# Ventilator.net
KiCad netlist of a schematic drawn in Altium Designer
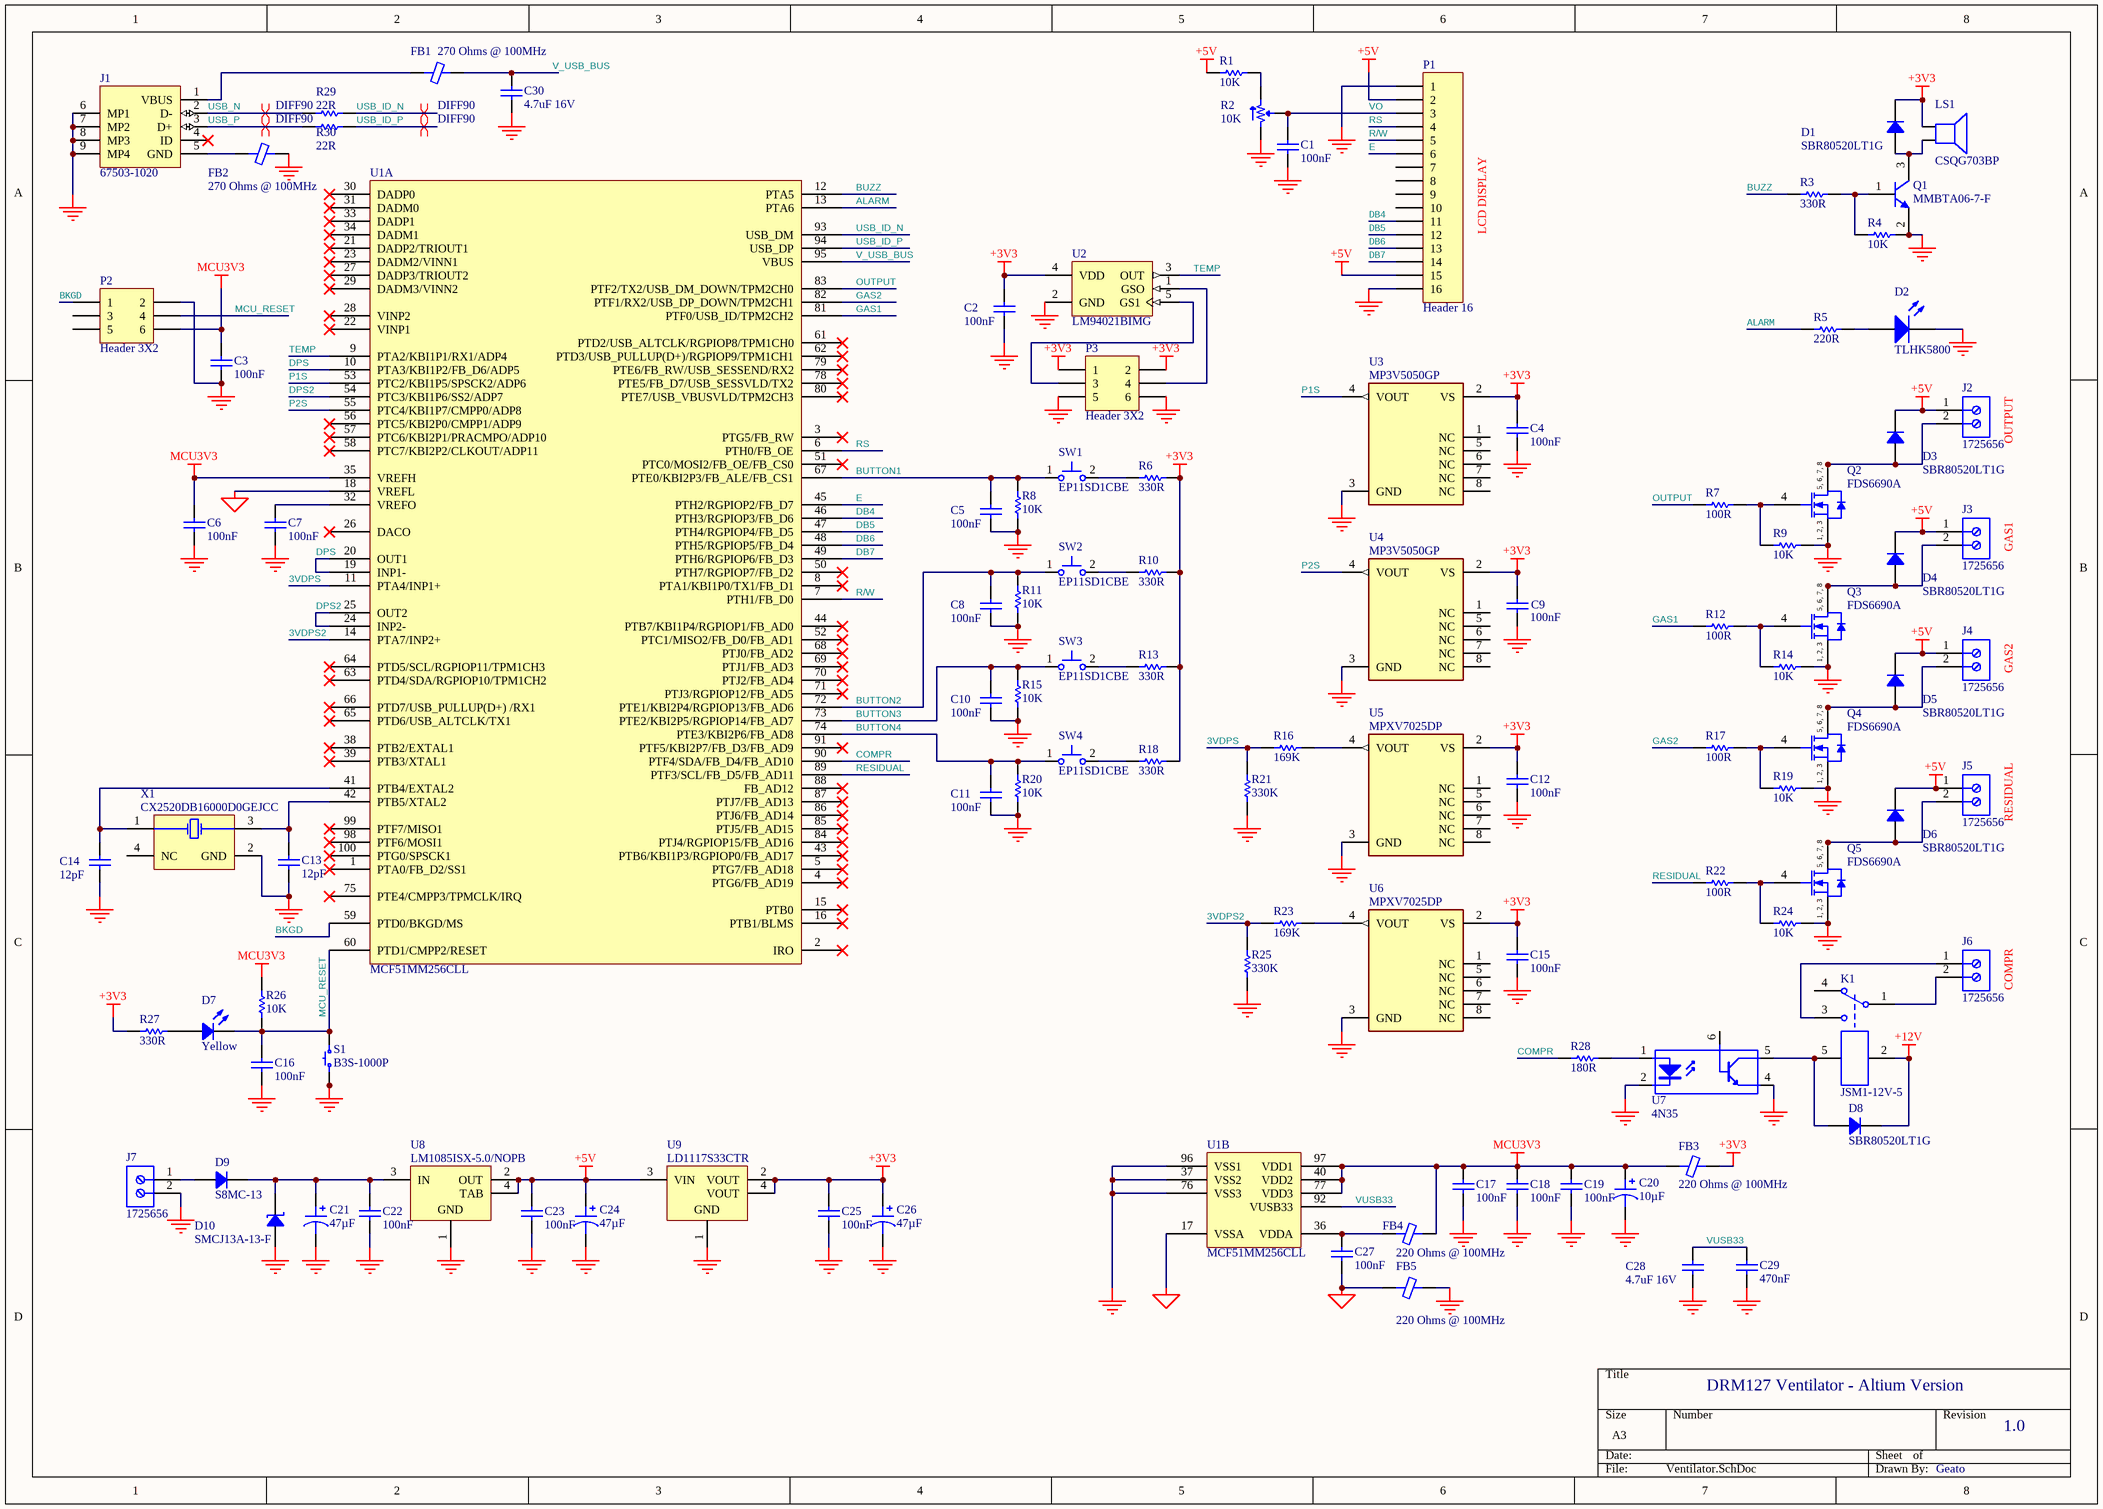
[diagram p0: Ventilator.SchDoc]

(export (version "E")
  (design (tool "Eeschema 10.0.6"))
  (components
    (comp (ref "C1")
      (value "100nF")
      (footprint "CAPC0603(1608)100_N")
      (description "CAP 100nF 50V ±10% 0603 (1608 Metric) Thickness 1mm SMD")
      (fields (field (name "TOLERANCE") "Â±10%"))
      (libsource (lib "Altium Content Vault") (part "CAP"))
    )
    (comp (ref "C2")
      (value "100nF")
      (footprint "CAPC0603(1608)100_N")
      (description "CAP 100nF 50V ±10% 0603 (1608 Metric) Thickness 1mm SMD")
      (fields (field (name "TOLERANCE") "Â±10%"))
      (libsource (lib "Altium Content Vault") (part "CAP"))
    )
    (comp (ref "C3")
      (value "100nF")
      (footprint "CAPC0603(1608)100_N")
      (description "CAP 100nF 50V ±10% 0603 (1608 Metric) Thickness 1mm SMD")
      (fields (field (name "TOLERANCE") "Â±10%"))
      (libsource (lib "Altium Content Vault") (part "CAP"))
    )
    (comp (ref "C4")
      (value "100nF")
      (footprint "CAPC0603(1608)100_N")
      (description "CAP 100nF 50V ±10% 0603 (1608 Metric) Thickness 1mm SMD")
      (fields (field (name "TOLERANCE") "Â±10%"))
      (libsource (lib "Altium Content Vault") (part "CAP"))
    )
    (comp (ref "C5")
      (value "100nF")
      (footprint "CAPC0603(1608)100_N")
      (description "CAP 100nF 50V ±10% 0603 (1608 Metric) Thickness 1mm SMD")
      (fields (field (name "TOLERANCE") "Â±10%"))
      (libsource (lib "Altium Content Vault") (part "CAP"))
    )
    (comp (ref "C6")
      (value "100nF")
      (footprint "CAPC0603(1608)100_N")
      (description "CAP 100nF 50V ±10% 0603 (1608 Metric) Thickness 1mm SMD")
      (fields (field (name "TOLERANCE") "Â±10%"))
      (libsource (lib "Altium Content Vault") (part "CAP"))
    )
    (comp (ref "C7")
      (value "100nF")
      (footprint "CAPC0603(1608)100_N")
      (description "CAP 100nF 50V ±10% 0603 (1608 Metric) Thickness 1mm SMD")
      (fields (field (name "TOLERANCE") "Â±10%"))
      (libsource (lib "Altium Content Vault") (part "CAP"))
    )
    (comp (ref "C8")
      (value "100nF")
      (footprint "CAPC0603(1608)100_N")
      (description "CAP 100nF 50V ±10% 0603 (1608 Metric) Thickness 1mm SMD")
      (fields (field (name "TOLERANCE") "Â±10%"))
      (libsource (lib "Altium Content Vault") (part "CAP"))
    )
    (comp (ref "C9")
      (value "100nF")
      (footprint "CAPC0603(1608)100_N")
      (description "CAP 100nF 50V ±10% 0603 (1608 Metric) Thickness 1mm SMD")
      (fields (field (name "TOLERANCE") "Â±10%"))
      (libsource (lib "Altium Content Vault") (part "CAP"))
    )
    (comp (ref "C10")
      (value "100nF")
      (footprint "CAPC0603(1608)100_N")
      (description "CAP 100nF 50V ±10% 0603 (1608 Metric) Thickness 1mm SMD")
      (fields (field (name "TOLERANCE") "Â±10%"))
      (libsource (lib "Altium Content Vault") (part "CAP"))
    )
    (comp (ref "C11")
      (value "100nF")
      (footprint "CAPC0603(1608)100_N")
      (description "CAP 100nF 50V ±10% 0603 (1608 Metric) Thickness 1mm SMD")
      (fields (field (name "TOLERANCE") "Â±10%"))
      (libsource (lib "Altium Content Vault") (part "CAP"))
    )
    (comp (ref "C12")
      (value "100nF")
      (footprint "CAPC0603(1608)100_N")
      (description "CAP 100nF 50V ±10% 0603 (1608 Metric) Thickness 1mm SMD")
      (fields (field (name "TOLERANCE") "Â±10%"))
      (libsource (lib "Altium Content Vault") (part "CAP"))
    )
    (comp (ref "C13")
      (value "12pF")
      (footprint "CAPC0603(1608)100_N")
      (description "CAP 12pF 50V ±0.5pF 0603 (1608 Metric) Thickness 1mm SMD")
      (fields (field (name "TOLERANCE") "Â±0.5pF"))
      (libsource (lib "Altium Content Vault") (part "CAP"))
    )
    (comp (ref "C14")
      (value "12pF")
      (footprint "CAPC0603(1608)100_N")
      (description "CAP 12pF 50V ±0.5pF 0603 (1608 Metric) Thickness 1mm SMD")
      (fields (field (name "TOLERANCE") "Â±0.5pF"))
      (libsource (lib "Altium Content Vault") (part "CAP"))
    )
    (comp (ref "C15")
      (value "100nF")
      (footprint "CAPC0603(1608)100_N")
      (description "CAP 100nF 50V ±10% 0603 (1608 Metric) Thickness 1mm SMD")
      (fields (field (name "TOLERANCE") "Â±10%"))
      (libsource (lib "Altium Content Vault") (part "CAP"))
    )
    (comp (ref "C16")
      (value "100nF")
      (footprint "CAPC0603(1608)100_N")
      (description "CAP 100nF 50V ±10% 0603 (1608 Metric) Thickness 1mm SMD")
      (fields (field (name "TOLERANCE") "Â±10%"))
      (libsource (lib "Altium Content Vault") (part "CAP"))
    )
    (comp (ref "C17")
      (value "100nF")
      (footprint "CAPC0603(1608)100_N")
      (description "CAP 100nF 50V ±10% 0603 (1608 Metric) Thickness 1mm SMD")
      (fields (field (name "TOLERANCE") "Â±10%"))
      (libsource (lib "Altium Content Vault") (part "CAP"))
    )
    (comp (ref "C18")
      (value "100nF")
      (footprint "CAPC0603(1608)100_N")
      (description "CAP 100nF 50V ±10% 0603 (1608 Metric) Thickness 1mm SMD")
      (fields (field (name "TOLERANCE") "Â±10%"))
      (libsource (lib "Altium Content Vault") (part "CAP"))
    )
    (comp (ref "C19")
      (value "100nF")
      (footprint "CAPC0603(1608)100_N")
      (description "CAP 100nF 50V ±10% 0603 (1608 Metric) Thickness 1mm SMD")
      (fields (field (name "TOLERANCE") "Â±10%"))
      (libsource (lib "Altium Content Vault") (part "CAP"))
    )
    (comp (ref "C20")
      (value "10µF")
      (footprint "CAP ALSMD 5.3MM H5.4MM")
      (description "CAP ALUM 10UF 20% 25V SMD")
      (fields
        (field (name "PART NUMBER") "EEE-1EA100SR")
        (field (name "MANUFACTURER") "Panasonic Electronic Components")
      )
      (libsource (lib "Altium Database Library V2") (part "Polarised Capacitor"))
    )
    (comp (ref "C21")
      (value "47µF")
      (footprint "CAP ALSMD 6.6MM H6.1MM")
      (description "CAP ALUM 47UF 20% 35V SMD")
      (fields (field (name "PART NUMBER") "UWT1V470MCL1GS") (field (name "MANUFACTURER") "Nichicon"))
      (libsource (lib "Altium Database Library V2") (part "Polarised Capacitor"))
    )
    (comp (ref "C22")
      (value "100nF")
      (footprint "CAPC0603(1608)100_N")
      (description "CAP 100nF 50V ±10% 0603 (1608 Metric) Thickness 1mm SMD")
      (fields (field (name "TOLERANCE") "Â±10%"))
      (libsource (lib "Altium Content Vault") (part "CAP"))
    )
    (comp (ref "C23")
      (value "100nF")
      (footprint "CAPC0603(1608)100_N")
      (description "CAP 100nF 50V ±10% 0603 (1608 Metric) Thickness 1mm SMD")
      (fields (field (name "TOLERANCE") "Â±10%"))
      (libsource (lib "Altium Content Vault") (part "CAP"))
    )
    (comp (ref "C24")
      (value "47µF")
      (footprint "CAP ALSMD 6.6MM H6.1MM")
      (description "CAP ALUM 47UF 20% 35V SMD")
      (fields (field (name "PART NUMBER") "UWT1V470MCL1GS") (field (name "MANUFACTURER") "Nichicon"))
      (libsource (lib "Altium Database Library V2") (part "Polarised Capacitor"))
    )
    (comp (ref "C25")
      (value "100nF")
      (footprint "CAPC0603(1608)100_N")
      (description "CAP 100nF 50V ±10% 0603 (1608 Metric) Thickness 1mm SMD")
      (fields (field (name "TOLERANCE") "Â±10%"))
      (libsource (lib "Altium Content Vault") (part "CAP"))
    )
    (comp (ref "C26")
      (value "47µF")
      (footprint "CAP ALSMD 6.6MM H6.1MM")
      (description "CAP ALUM 47UF 20% 35V SMD")
      (fields (field (name "PART NUMBER") "UWT1V470MCL1GS") (field (name "MANUFACTURER") "Nichicon"))
      (libsource (lib "Altium Database Library V2") (part "Polarised Capacitor"))
    )
    (comp (ref "C27")
      (value "100nF")
      (footprint "CAPC0603(1608)100_N")
      (description "CAP 100nF 50V ±10% 0603 (1608 Metric) Thickness 1mm SMD")
      (fields (field (name "TOLERANCE") "Â±10%"))
      (libsource (lib "Altium Content Vault") (part "CAP"))
    )
    (comp (ref "C28")
      (value "4.7uF 16V")
      (footprint "CAPC0805(2012)145_N")
      (description "CAP 4.7uF 16V ±20% 0805 (2012 Metric) Thickness 1.45mm SMD")
      (fields (field (name "TOLERANCE") "Â±20%"))
      (libsource (lib "Altium Content Vault") (part "CAP"))
    )
    (comp (ref "C29")
      (value "470nF")
      (footprint "CAPC0805(2012)145_N")
      (description "CAP 470nF 50V ±10% 0805 (2012 Metric) Thickness 1.45mm SMD")
      (fields (field (name "TOLERANCE") "Â±10%"))
      (libsource (lib "Altium Content Vault") (part "CAP"))
    )
    (comp (ref "C30")
      (value "4.7uF 16V")
      (footprint "CAPC0805(2012)145_N")
      (description "CAP 4.7uF 16V ±20% 0805 (2012 Metric) Thickness 1.45mm SMD")
      (fields (field (name "TOLERANCE") "Â±20%"))
      (libsource (lib "Altium Content Vault") (part "CAP"))
    )
    (comp (ref "D1")
      (value "SBR80520LT1G")
      (footprint "SOD-123")
      (description "DIODE SCHOTTKY 20V 500MA SOD123")
      (fields (field (name "MANUFACTURER") "ON Semiconductor"))
      (libsource (lib "Altium Database Library V2") (part "Diode"))
    )
    (comp (ref "D2")
      (value "TLHK5800")
      (footprint "LED T-13/4")
      (description "T-13/4 LED")
      (fields (field (name "PUBLISHER") "Altium Limited"))
      (libsource (lib "Miscellaneous Devices") (part "LED0"))
    )
    (comp (ref "D3")
      (value "SBR80520LT1G")
      (footprint "SOD-123")
      (description "DIODE SCHOTTKY 20V 500MA SOD123")
      (fields (field (name "MANUFACTURER") "ON Semiconductor"))
      (libsource (lib "Altium Database Library V2") (part "Diode"))
    )
    (comp (ref "D4")
      (value "SBR80520LT1G")
      (footprint "SOD-123")
      (description "DIODE SCHOTTKY 20V 500MA SOD123")
      (fields (field (name "MANUFACTURER") "ON Semiconductor"))
      (libsource (lib "Altium Database Library V2") (part "Diode"))
    )
    (comp (ref "D5")
      (value "SBR80520LT1G")
      (footprint "SOD-123")
      (description "DIODE SCHOTTKY 20V 500MA SOD123")
      (fields (field (name "MANUFACTURER") "ON Semiconductor"))
      (libsource (lib "Altium Database Library V2") (part "Diode"))
    )
    (comp (ref "D6")
      (value "SBR80520LT1G")
      (footprint "SOD-123")
      (description "DIODE SCHOTTKY 20V 500MA SOD123")
      (fields (field (name "MANUFACTURER") "ON Semiconductor"))
      (libsource (lib "Altium Database Library V2") (part "Diode"))
    )
    (comp (ref "D7")
      (value "Yellow")
      (footprint "LED 0603_1608 YELLOW")
      (description "LED YELLOW DIFFUSED 0603 SMD")
      (fields (field (name "PART NUMBER") "5975223407F") (field (name "MANUFACTURER") "Dialight"))
      (libsource (lib "Altium Database Library V2") (part "LED"))
    )
    (comp (ref "D8")
      (value "SBR80520LT1G")
      (footprint "SOD-123")
      (description "DIODE SCHOTTKY 20V 500MA SOD123")
      (fields (field (name "MANUFACTURER") "ON Semiconductor"))
      (libsource (lib "Altium Database Library V2") (part "Diode"))
    )
    (comp (ref "D9")
      (value "S8MC-13")
      (footprint "DO214AB SMC")
      (description "DIODE GEN PURP 1KV 8A SMC")
      (fields (field (name "MANUFACTURER") "Diodes Incorporated"))
      (libsource (lib "Altium Database Library V2") (part "Diode"))
    )
    (comp (ref "D10")
      (value "SMCJ13A-13-F")
      (footprint "DO214AB SMC")
      (description "TVS DIODE 13V 21.5V SMC")
      (fields (field (name "MANUFACTURER") "Diodes Incorporated"))
      (libsource (lib "Altium Database Library V2") (part "DIODE TVS UNI"))
    )
    (comp (ref "FB1")
      (value "270 Ohms @ 100MHz")
      (footprint "FER 0603_1608")
      (description "FERRITE BEAD 270 OHM 0603 1LN")
      (fields (field (name "PART NUMBER") "BKP1608HS271-T") (field (name "MANUFACTURER") "Taiyo Yuden"))
      (libsource (lib "Altium Database Library V2") (part "Ferrite Chip"))
    )
    (comp (ref "FB2")
      (value "270 Ohms @ 100MHz")
      (footprint "FER 0603_1608")
      (description "FERRITE BEAD 270 OHM 0603 1LN")
      (fields (field (name "PART NUMBER") "BKP1608HS271-T") (field (name "MANUFACTURER") "Taiyo Yuden"))
      (libsource (lib "Altium Database Library V2") (part "Ferrite Chip"))
    )
    (comp (ref "FB3")
      (value "220 Ohms @ 100MHz")
      (footprint "FER 0805_2012")
      (description "FERRITE BEAD 220 OHM 0805 1LN")
      (fields
        (field (name "PART NUMBER") "BLM21PG221SN1D")
        (field (name "MANUFACTURER") "Murata Electronics")
      )
      (libsource (lib "Altium Database Library V2") (part "Ferrite Chip"))
    )
    (comp (ref "FB4")
      (value "220 Ohms @ 100MHz")
      (footprint "FER 0805_2012")
      (description "FERRITE BEAD 220 OHM 0805 1LN")
      (fields
        (field (name "PART NUMBER") "BLM21PG221SN1D")
        (field (name "MANUFACTURER") "Murata Electronics")
      )
      (libsource (lib "Altium Database Library V2") (part "Ferrite Chip"))
    )
    (comp (ref "FB5")
      (value "220 Ohms @ 100MHz")
      (footprint "FER 0805_2012")
      (description "FERRITE BEAD 220 OHM 0805 1LN")
      (fields
        (field (name "PART NUMBER") "BLM21PG221SN1D")
        (field (name "MANUFACTURER") "Murata Electronics")
      )
      (libsource (lib "Altium Database Library V2") (part "Ferrite Chip"))
    )
    (comp (ref "J1")
      (value "67503-1020")
      (footprint "MOLX-67503-1020_V")
      (description "USB, MINI, SMD, RA KME04-USBMU03A01")
      (fields (field (name "MANUFACTURER") "Molex"))
      (libsource (lib "Altium Inc") (part "MOLX-67503-1020"))
    )
    (comp (ref "J2")
      (value "1725656")
      (footprint "PHOE-1725656-2")
      (description "Male Header, Pitch 2.54 mm, 1 x 2 Position, Height 9 mm, Tail Length 3.5 mm")
      (fields (field (name "MANUFACTURER") "Phoenix Contact"))
      (libsource (lib "Altium Content Vault") (part "CN-1P-F-TB2"))
    )
    (comp (ref "J3")
      (value "1725656")
      (footprint "PHOE-1725656-2")
      (description "Male Header, Pitch 2.54 mm, 1 x 2 Position, Height 9 mm, Tail Length 3.5 mm")
      (fields (field (name "MANUFACTURER") "Phoenix Contact"))
      (libsource (lib "Altium Content Vault") (part "CN-1P-F-TB2"))
    )
    (comp (ref "J4")
      (value "1725656")
      (footprint "PHOE-1725656-2")
      (description "Male Header, Pitch 2.54 mm, 1 x 2 Position, Height 9 mm, Tail Length 3.5 mm")
      (fields (field (name "MANUFACTURER") "Phoenix Contact"))
      (libsource (lib "Altium Content Vault") (part "CN-1P-F-TB2"))
    )
    (comp (ref "J5")
      (value "1725656")
      (footprint "PHOE-1725656-2")
      (description "Male Header, Pitch 2.54 mm, 1 x 2 Position, Height 9 mm, Tail Length 3.5 mm")
      (fields (field (name "MANUFACTURER") "Phoenix Contact"))
      (libsource (lib "Altium Content Vault") (part "CN-1P-F-TB2"))
    )
    (comp (ref "J6")
      (value "1725656")
      (footprint "PHOE-1725656-2")
      (description "Male Header, Pitch 2.54 mm, 1 x 2 Position, Height 9 mm, Tail Length 3.5 mm")
      (fields (field (name "MANUFACTURER") "Phoenix Contact"))
      (libsource (lib "Altium Content Vault") (part "CN-1P-F-TB2"))
    )
    (comp (ref "J7")
      (value "1725656")
      (footprint "PHOE-1725656-2")
      (description "Male Header, Pitch 2.54 mm, 1 x 2 Position, Height 9 mm, Tail Length 3.5 mm")
      (fields (field (name "MANUFACTURER") "Phoenix Contact"))
      (libsource (lib "Altium Content Vault") (part "CN-1P-F-TB2"))
    )
    (comp (ref "K1")
      (value "JSM1-12V-5")
      (footprint "PNSC-JSM1-12V-5_V")
      (fields (field (name "MANUFACTURER") "Panasonic") (field (name "APPROVAL BODIES") "CSA/TUV/UL"))
      (libsource (lib "Altium Content Vault") (part "RELAY-SPDT-5_E"))
    )
    (comp (ref "LS1")
      (value "CSQG703BP")
      (footprint "CSQG703BP")
      (description "Loudspeaker")
      (fields (field (name "PUBLISHER") "Altium Limited"))
      (libsource (lib "Miscellaneous Devices") (part "Speaker"))
    )
    (comp (ref "P1")
      (value "Header 16")
      (footprint "NHD-0420DZ-FSW-FBW")
      (description "Header, 16-Pin")
      (fields (field (name "PUBLISHER") "Altium Limited"))
      (libsource (lib "Miscellaneous Connectors") (part "Header 16"))
    )
    (comp (ref "P2")
      (value "Header 3X2")
      (footprint "HDR2X3")
      (description "Header, 3-Pin, Dual row")
      (fields (field (name "PUBLISHER") "Altium Limited"))
      (libsource (lib "Miscellaneous Connectors") (part "Header 3X2"))
    )
    (comp (ref "P3")
      (value "Header 3X2")
      (footprint "HDR2X3")
      (description "Header, 3-Pin, Dual row")
      (fields (field (name "PUBLISHER") "Altium Limited"))
      (libsource (lib "Miscellaneous Connectors") (part "Header 3X2"))
    )
    (comp (ref "Q1")
      (value "MMBTA06-7-F")
      (footprint "DIOD-SOT23-3_V")
      (description "NPN Small Signal Transistor, 80 V, -55 to 150 degC, 3-Pin SOT23, RoHS, Tape and Reel")
      (fields (field (name "MANUFACTURER") "DiodesIncorporated"))
      (libsource (lib "Altium Content Vault") (part "BJT-NPN-BEC-3"))
    )
    (comp (ref "Q2")
      (value "FDS6690A")
      (footprint "FAIR-SOIC-8_V")
      (fields (field (name "MANUFACTURER") "Fairchild Semiconductor"))
      (libsource (lib "Altium Content Vault") (part "NEMOS-SSSGDDDD-8"))
    )
    (comp (ref "Q3")
      (value "FDS6690A")
      (footprint "FAIR-SOIC-8_V")
      (fields (field (name "MANUFACTURER") "Fairchild Semiconductor"))
      (libsource (lib "Altium Content Vault") (part "NEMOS-SSSGDDDD-8"))
    )
    (comp (ref "Q4")
      (value "FDS6690A")
      (footprint "FAIR-SOIC-8_V")
      (fields (field (name "MANUFACTURER") "Fairchild Semiconductor"))
      (libsource (lib "Altium Content Vault") (part "NEMOS-SSSGDDDD-8"))
    )
    (comp (ref "Q5")
      (value "FDS6690A")
      (footprint "FAIR-SOIC-8_V")
      (fields (field (name "MANUFACTURER") "Fairchild Semiconductor"))
      (libsource (lib "Altium Content Vault") (part "NEMOS-SSSGDDDD-8"))
    )
    (comp (ref "R1")
      (value "10K")
      (footprint "RESC0603(1608)_N")
      (description "10K 0.1W 5% 0603 (1608 Metric)  SMD")
      (fields (field (name "TOLERANCE") "5 %") (field (name "POWER") "0.1 W"))
      (libsource (lib "Altium Content Vault") (part "RES"))
    )
    (comp (ref "R2")
      (value "10K")
      (footprint "POT BOURNS TRIMPOT TC33")
      (description "TRIMMER 10K OHM 0.1W J LEAD TOP")
      (fields (field (name "PART NUMBER") "TC33X-1-103E") (field (name "MANUFACTURER") "Bourns Inc."))
      (libsource (lib "Altium Database Library V2") (part "Potentiometer"))
    )
    (comp (ref "R3")
      (value "330R")
      (footprint "RESC0603(1608)_N")
      (description "330R 0.1W 5% 0603 (1608 Metric)  SMD")
      (fields (field (name "TOLERANCE") "5 %") (field (name "POWER") "0.1 W"))
      (libsource (lib "Altium Content Vault") (part "RES"))
    )
    (comp (ref "R4")
      (value "10K")
      (footprint "RESC0603(1608)_N")
      (description "10K 0.1W 5% 0603 (1608 Metric)  SMD")
      (fields (field (name "TOLERANCE") "5 %") (field (name "POWER") "0.1 W"))
      (libsource (lib "Altium Content Vault") (part "RES"))
    )
    (comp (ref "R5")
      (value "220R")
      (footprint "RESC0603(1608)_N")
      (description "220R 0.1W 5% 0603 (1608 Metric)  SMD")
      (fields (field (name "POWER") "0.1 W") (field (name "TOLERANCE") "5 %"))
      (libsource (lib "Altium Content Vault") (part "RES"))
    )
    (comp (ref "R6")
      (value "330R")
      (footprint "RESC0603(1608)_N")
      (description "330R 0.1W 5% 0603 (1608 Metric)  SMD")
      (fields (field (name "TOLERANCE") "5 %") (field (name "POWER") "0.1 W"))
      (libsource (lib "Altium Content Vault") (part "RES"))
    )
    (comp (ref "R7")
      (value "100R")
      (footprint "RESC0603(1608)_N")
      (description "100R 0.1W 5% 0603 (1608 Metric)  SMD")
      (fields (field (name "TOLERANCE") "5 %") (field (name "POWER") "0.1 W"))
      (libsource (lib "Altium Content Vault") (part "RES"))
    )
    (comp (ref "R8")
      (value "10K")
      (footprint "RESC0603(1608)_N")
      (description "10K 0.1W 5% 0603 (1608 Metric)  SMD")
      (fields (field (name "TOLERANCE") "5 %") (field (name "POWER") "0.1 W"))
      (libsource (lib "Altium Content Vault") (part "RES"))
    )
    (comp (ref "R9")
      (value "10K")
      (footprint "RESC0603(1608)_N")
      (description "10K 0.1W 5% 0603 (1608 Metric)  SMD")
      (fields (field (name "TOLERANCE") "5 %") (field (name "POWER") "0.1 W"))
      (libsource (lib "Altium Content Vault") (part "RES"))
    )
    (comp (ref "R10")
      (value "330R")
      (footprint "RESC0603(1608)_N")
      (description "330R 0.1W 5% 0603 (1608 Metric)  SMD")
      (fields (field (name "TOLERANCE") "5 %") (field (name "POWER") "0.1 W"))
      (libsource (lib "Altium Content Vault") (part "RES"))
    )
    (comp (ref "R11")
      (value "10K")
      (footprint "RESC0603(1608)_N")
      (description "10K 0.1W 5% 0603 (1608 Metric)  SMD")
      (fields (field (name "TOLERANCE") "5 %") (field (name "POWER") "0.1 W"))
      (libsource (lib "Altium Content Vault") (part "RES"))
    )
    (comp (ref "R12")
      (value "100R")
      (footprint "RESC0603(1608)_N")
      (description "100R 0.1W 5% 0603 (1608 Metric)  SMD")
      (fields (field (name "TOLERANCE") "5 %") (field (name "POWER") "0.1 W"))
      (libsource (lib "Altium Content Vault") (part "RES"))
    )
    (comp (ref "R13")
      (value "330R")
      (footprint "RESC0603(1608)_N")
      (description "330R 0.1W 5% 0603 (1608 Metric)  SMD")
      (fields (field (name "TOLERANCE") "5 %") (field (name "POWER") "0.1 W"))
      (libsource (lib "Altium Content Vault") (part "RES"))
    )
    (comp (ref "R14")
      (value "10K")
      (footprint "RESC0603(1608)_N")
      (description "10K 0.1W 5% 0603 (1608 Metric)  SMD")
      (fields (field (name "TOLERANCE") "5 %") (field (name "POWER") "0.1 W"))
      (libsource (lib "Altium Content Vault") (part "RES"))
    )
    (comp (ref "R15")
      (value "10K")
      (footprint "RESC0603(1608)_N")
      (description "10K 0.1W 5% 0603 (1608 Metric)  SMD")
      (fields (field (name "TOLERANCE") "5 %") (field (name "POWER") "0.1 W"))
      (libsource (lib "Altium Content Vault") (part "RES"))
    )
    (comp (ref "R16")
      (value "169K")
      (footprint "RESC0603(1608)_N")
      (description "169K 0.1W 1% 0603 (1608 Metric)  SMD")
      (fields (field (name "TOLERANCE") "1 %") (field (name "POWER") "0.1 W"))
      (libsource (lib "Altium Content Vault") (part "RES"))
    )
    (comp (ref "R17")
      (value "100R")
      (footprint "RESC0603(1608)_N")
      (description "100R 0.1W 5% 0603 (1608 Metric)  SMD")
      (fields (field (name "TOLERANCE") "5 %") (field (name "POWER") "0.1 W"))
      (libsource (lib "Altium Content Vault") (part "RES"))
    )
    (comp (ref "R18")
      (value "330R")
      (footprint "RESC0603(1608)_N")
      (description "330R 0.1W 5% 0603 (1608 Metric)  SMD")
      (fields (field (name "TOLERANCE") "5 %") (field (name "POWER") "0.1 W"))
      (libsource (lib "Altium Content Vault") (part "RES"))
    )
    (comp (ref "R19")
      (value "10K")
      (footprint "RESC0603(1608)_N")
      (description "10K 0.1W 5% 0603 (1608 Metric)  SMD")
      (fields (field (name "TOLERANCE") "5 %") (field (name "POWER") "0.1 W"))
      (libsource (lib "Altium Content Vault") (part "RES"))
    )
    (comp (ref "R20")
      (value "10K")
      (footprint "RESC0603(1608)_N")
      (description "10K 0.1W 5% 0603 (1608 Metric)  SMD")
      (fields (field (name "TOLERANCE") "5 %") (field (name "POWER") "0.1 W"))
      (libsource (lib "Altium Content Vault") (part "RES"))
    )
    (comp (ref "R21")
      (value "330K")
      (footprint "RESC0603(1608)_N")
      (description "330K 0.1W 1% 0603 (1608 Metric)  SMD")
      (fields (field (name "POWER") "0.1 W") (field (name "TOLERANCE") "1 %"))
      (libsource (lib "Altium Content Vault") (part "RES"))
    )
    (comp (ref "R22")
      (value "100R")
      (footprint "RESC0603(1608)_N")
      (description "100R 0.1W 5% 0603 (1608 Metric)  SMD")
      (fields (field (name "TOLERANCE") "5 %") (field (name "POWER") "0.1 W"))
      (libsource (lib "Altium Content Vault") (part "RES"))
    )
    (comp (ref "R23")
      (value "169K")
      (footprint "RESC0603(1608)_N")
      (description "169K 0.1W 1% 0603 (1608 Metric)  SMD")
      (fields (field (name "TOLERANCE") "1 %") (field (name "POWER") "0.1 W"))
      (libsource (lib "Altium Content Vault") (part "RES"))
    )
    (comp (ref "R24")
      (value "10K")
      (footprint "RESC0603(1608)_N")
      (description "10K 0.1W 5% 0603 (1608 Metric)  SMD")
      (fields (field (name "TOLERANCE") "5 %") (field (name "POWER") "0.1 W"))
      (libsource (lib "Altium Content Vault") (part "RES"))
    )
    (comp (ref "R25")
      (value "330K")
      (footprint "RESC0603(1608)_N")
      (description "330K 0.1W 1% 0603 (1608 Metric)  SMD")
      (fields (field (name "POWER") "0.1 W") (field (name "TOLERANCE") "1 %"))
      (libsource (lib "Altium Content Vault") (part "RES"))
    )
    (comp (ref "R26")
      (value "10K")
      (footprint "RESC0603(1608)_N")
      (description "10K 0.1W 5% 0603 (1608 Metric)  SMD")
      (fields (field (name "TOLERANCE") "5 %") (field (name "POWER") "0.1 W"))
      (libsource (lib "Altium Content Vault") (part "RES"))
    )
    (comp (ref "R27")
      (value "330R")
      (footprint "RESC0603(1608)_N")
      (description "330R 0.1W 5% 0603 (1608 Metric)  SMD")
      (fields (field (name "TOLERANCE") "5 %") (field (name "POWER") "0.1 W"))
      (libsource (lib "Altium Content Vault") (part "RES"))
    )
    (comp (ref "R28")
      (value "180R")
      (footprint "RESC0603(1608)_N")
      (description "180R 0.1W 5% 0603 (1608 Metric)  SMD")
      (fields (field (name "POWER") "0.1 W") (field (name "TOLERANCE") "5 %"))
      (libsource (lib "Altium Content Vault") (part "RES"))
    )
    (comp (ref "R29")
      (value "22R")
      (footprint "RESC0603(1608)_N")
      (description "22R 0.1W 5% 0603 (1608 Metric)  SMD")
      (fields (field (name "POWER") "0.1 W") (field (name "TOLERANCE") "5 %"))
      (libsource (lib "Altium Content Vault") (part "RES"))
    )
    (comp (ref "R30")
      (value "22R")
      (footprint "RESC0603(1608)_N")
      (description "22R 0.1W 5% 0603 (1608 Metric)  SMD")
      (fields (field (name "POWER") "0.1 W") (field (name "TOLERANCE") "5 %"))
      (libsource (lib "Altium Content Vault") (part "RES"))
    )
    (comp (ref "S1")
      (value "B3S-1000P")
      (footprint "OMRON B3S-1000P")
      (description "SWITCH TACTILE SPST-NO 0.05A 24V")
      (fields (field (name "MANUFACTURER") "Omron Electronics Inc-EMC Div"))
      (libsource (lib "Altium Database Library V2") (part "SPST-NO 4 PIN"))
    )
    (comp (ref "SW1")
      (value "EP11SD1CBE")
      (footprint "EP11SD1CBE")
      (description "EP Series Sealed Pushbutton Switches")
      (fields (field (name "PUBLISHER") "Altium Limited"))
      (libsource (lib "CK Switch") (part "EP11SD1CBE"))
    )
    (comp (ref "SW2")
      (value "EP11SD1CBE")
      (footprint "EP11SD1CBE")
      (description "EP Series Sealed Pushbutton Switches")
      (fields (field (name "PUBLISHER") "Altium Limited"))
      (libsource (lib "CK Switch") (part "EP11SD1CBE"))
    )
    (comp (ref "SW3")
      (value "EP11SD1CBE")
      (footprint "EP11SD1CBE")
      (description "EP Series Sealed Pushbutton Switches")
      (fields (field (name "PUBLISHER") "Altium Limited"))
      (libsource (lib "CK Switch") (part "EP11SD1CBE"))
    )
    (comp (ref "SW4")
      (value "EP11SD1CBE")
      (footprint "EP11SD1CBE")
      (description "EP Series Sealed Pushbutton Switches")
      (fields (field (name "PUBLISHER") "Altium Limited"))
      (libsource (lib "CK Switch") (part "EP11SD1CBE"))
    )
    (comp (ref "U1")
      (value "MCF51MM256CLL")
      (footprint "TSQFP50P1600X1600X140-100N")
      (description "32-bit Coldfire Freescale MCU")
      (libsource (lib "Pathfinder") (part "MCF51MM256CLL"))
    )
    (comp (ref "U2")
      (value "LM94021BIMG")
      (footprint "DCK0005A_N")
      (description "Multi-Gain Analog Temperature Sensor, 5-pin SC-70")
      (fields (field (name "MANUFACTURER") "Texas Instruments"))
      (libsource (lib "Altium Content Vault") (part "SEN-TEMP-LM94021BIMG-5"))
    )
    (comp (ref "U3")
      (value "MP3V5050GP")
      (footprint "NXP_Semiconductor_98ASA99303D_MFG")
      (libsource (lib "IC_NXP_Semiconductor_MP3V5050GP_eec") (part "MP3V5050GP"))
    )
    (comp (ref "U4")
      (value "MP3V5050GP")
      (footprint "NXP_Semiconductor_98ASA99303D_MFG")
      (libsource (lib "IC_NXP_Semiconductor_MP3V5050GP_eec") (part "MP3V5050GP"))
    )
    (comp (ref "U5")
      (value "MPXV7025DP")
      (footprint "MPXVxxxxDP")
      (description "+/- 25 kPa Differential Pressure Sensor")
      (libsource (lib "IC_NXP_Semiconductor_MP3V5050GP_eec") (part "MPXV7025DP"))
    )
    (comp (ref "U6")
      (value "MPXV7025DP")
      (footprint "MPXVxxxxDP")
      (description "+/- 25 kPa Differential Pressure Sensor")
      (libsource (lib "IC_NXP_Semiconductor_MP3V5050GP_eec") (part "MPXV7025DP"))
    )
    (comp (ref "U7")
      (value "4N35")
      (footprint "SMD-6")
      (description "6Pin Optocoupler")
      (fields (field (name "PUBLISHER") "Altium Limited"))
      (libsource (lib "Engineered Air") (part "Optoisolator"))
    )
    (comp (ref "U8")
      (value "LM1085ISX-5.0/NOPB")
      (footprint "KTT0003B_N")
      (description "3A Low Dropout Positive Regulators, 3-pin TO-263, Pb-Free")
      (fields (field (name "MANUFACTURER") "Texas Instruments"))
      (libsource (lib "Altium Content Vault") (part "PM-REG-LM1086-SOT4"))
    )
    (comp (ref "U9")
      (value "LD1117S33CTR")
      (footprint "SOT-223_N")
      (description "Fixed Low Drop Positive Voltage Regulator, 3.3V, 4-Pin SOT-223, Tape and Reel")
      (libsource (lib "Altium Content Vault") (part "PM-REG-LD1117-SOT4"))
    )
    (comp (ref "X1")
      (value "CX2520DB16000D0GEJCC")
      (footprint "AVX-CX2520DB_V")
      (description "Crystal, 16 MHz, 8 pF, -10 to 70 degC, 4-Pin SMD, RoHS, Tape and Reel")
      (fields (field (name "MANUFACTURER") "AVX") (field (name "TOLERANCE") "15PPM"))
      (libsource (lib "Altium Content Vault") (part "XTAL-1-3-4_A"))
    )
  )
  (nets
    (net (code "1") (name "+3V3") (class "Default")
      (node (ref "C12") (pin "1") (pinfunction "1_1") (pintype "passive"))
      (node (ref "C15") (pin "1") (pinfunction "1_1") (pintype "passive"))
      (node (ref "C2") (pin "1") (pinfunction "1_1") (pintype "passive"))
      (node (ref "C25") (pin "1") (pinfunction "1_1") (pintype "passive"))
      (node (ref "C26") (pin "1") (pinfunction "1_1") (pintype "passive"))
      (node (ref "C4") (pin "1") (pinfunction "1_1") (pintype "passive"))
      (node (ref "C9") (pin "1") (pinfunction "1_1") (pintype "passive"))
      (node (ref "D1") (pin "2") (pinfunction "2_2") (pintype "passive"))
      (node (ref "FB3") (pin "1") (pinfunction "1_1") (pintype "passive"))
      (node (ref "LS1") (pin "1") (pinfunction "1_1") (pintype "passive"))
      (node (ref "P3") (pin "1") (pinfunction "1_1") (pintype "passive"))
      (node (ref "P3") (pin "2") (pinfunction "2_2") (pintype "passive"))
      (node (ref "R10") (pin "2") (pinfunction "2_2") (pintype "passive"))
      (node (ref "R13") (pin "2") (pinfunction "2_2") (pintype "passive"))
      (node (ref "R18") (pin "2") (pinfunction "2_2") (pintype "passive"))
      (node (ref "R27") (pin "1") (pinfunction "1_1") (pintype "passive"))
      (node (ref "R6") (pin "2") (pinfunction "2_2") (pintype "passive"))
      (node (ref "U2") (pin "4") (pinfunction "VDD_4") (pintype "power_in"))
      (node (ref "U3") (pin "2") (pinfunction "VS_2") (pintype "power_in"))
      (node (ref "U4") (pin "2") (pinfunction "VS_2") (pintype "power_in"))
      (node (ref "U5") (pin "2") (pinfunction "VS_2") (pintype "power_in"))
      (node (ref "U6") (pin "2") (pinfunction "VS_2") (pintype "power_in"))
      (node (ref "U9") (pin "2") (pinfunction "VOUT_2") (pintype "power_in"))
      (node (ref "U9") (pin "4") (pinfunction "VOUT_4") (pintype "power_in"))
    )
    (net (code "2") (name "+5V") (class "Default")
      (node (ref "C23") (pin "1") (pinfunction "1_1") (pintype "passive"))
      (node (ref "C24") (pin "1") (pinfunction "1_1") (pintype "passive"))
      (node (ref "D3") (pin "2") (pinfunction "2_2") (pintype "passive"))
      (node (ref "D4") (pin "2") (pinfunction "2_2") (pintype "passive"))
      (node (ref "D5") (pin "2") (pinfunction "2_2") (pintype "passive"))
      (node (ref "D6") (pin "2") (pinfunction "2_2") (pintype "passive"))
      (node (ref "J2") (pin "1") (pinfunction "1_1") (pintype "passive"))
      (node (ref "J3") (pin "1") (pinfunction "1_1") (pintype "passive"))
      (node (ref "J4") (pin "1") (pinfunction "1_1") (pintype "passive"))
      (node (ref "J5") (pin "1") (pinfunction "1_1") (pintype "passive"))
      (node (ref "P1") (pin "15") (pinfunction "15_15") (pintype "passive"))
      (node (ref "P1") (pin "2") (pinfunction "2_2") (pintype "passive"))
      (node (ref "R1") (pin "1") (pinfunction "1_1") (pintype "passive"))
      (node (ref "U8") (pin "2") (pinfunction "OUT_2") (pintype "power_in"))
      (node (ref "U8") (pin "4") (pinfunction "TAB_4") (pintype "power_in"))
      (node (ref "U9") (pin "3") (pinfunction "VIN_3") (pintype "power_in"))
    )
    (net (code "3") (name "+12V") (class "Default")
      (node (ref "D8") (pin "2") (pinfunction "2_2") (pintype "passive"))
      (node (ref "K1") (pin "2") (pinfunction "2_2") (pintype "passive"))
    )
    (net (code "4") (name "/3VDPS") (class "Default")
      (node (ref "R16") (pin "1") (pinfunction "1_1") (pintype "passive"))
      (node (ref "R21") (pin "2") (pinfunction "2_2") (pintype "passive"))
      (node (ref "U1") (pin "11") (pinfunction "PTA4/INP1+_11") (pintype "passive"))
    )
    (net (code "5") (name "/3VDPS2") (class "Default")
      (node (ref "R23") (pin "1") (pinfunction "1_1") (pintype "passive"))
      (node (ref "R25") (pin "2") (pinfunction "2_2") (pintype "passive"))
      (node (ref "U1") (pin "14") (pinfunction "PTA7/INP2+_14") (pintype "passive"))
    )
    (net (code "6") (name "/ALARM") (class "Default")
      (node (ref "R5") (pin "1") (pinfunction "1_1") (pintype "passive"))
      (node (ref "U1") (pin "13") (pinfunction "PTA6_13") (pintype "passive"))
    )
    (net (code "7") (name "/BKGD") (class "Default")
      (node (ref "P2") (pin "1") (pinfunction "1_1") (pintype "passive"))
      (node (ref "U1") (pin "59") (pinfunction "PTD0/BKGD/MS_59") (pintype "passive"))
    )
    (net (code "8") (name "/BUTTON1") (class "Default")
      (node (ref "C5") (pin "1") (pinfunction "1_1") (pintype "passive"))
      (node (ref "R8") (pin "2") (pinfunction "2_2") (pintype "passive"))
      (node (ref "SW1") (pin "1") (pinfunction "1_1") (pintype "passive"))
      (node (ref "U1") (pin "67") (pinfunction "PTE0/KBI2P3/FB_ALE/FB_CS1_67") (pintype "passive"))
    )
    (net (code "9") (name "/BUTTON2") (class "Default")
      (node (ref "C8") (pin "1") (pinfunction "1_1") (pintype "passive"))
      (node (ref "R11") (pin "2") (pinfunction "2_2") (pintype "passive"))
      (node (ref "SW2") (pin "1") (pinfunction "1_1") (pintype "passive"))
      (node (ref "U1") (pin "72") (pinfunction "PTE1/KBI2P4/RGPIOP13/FB_AD6_72") (pintype "passive"))
    )
    (net (code "10") (name "/BUTTON3") (class "Default")
      (node (ref "C10") (pin "1") (pinfunction "1_1") (pintype "passive"))
      (node (ref "R15") (pin "2") (pinfunction "2_2") (pintype "passive"))
      (node (ref "SW3") (pin "1") (pinfunction "1_1") (pintype "passive"))
      (node (ref "U1") (pin "73") (pinfunction "PTE2/KBI2P5/RGPIOP14/FB_AD7_73") (pintype "passive"))
    )
    (net (code "11") (name "/BUTTON4") (class "Default")
      (node (ref "C11") (pin "1") (pinfunction "1_1") (pintype "passive"))
      (node (ref "R20") (pin "2") (pinfunction "2_2") (pintype "passive"))
      (node (ref "SW4") (pin "1") (pinfunction "1_1") (pintype "passive"))
      (node (ref "U1") (pin "74") (pinfunction "PTE3/KBI2P6/FB_AD8_74") (pintype "passive"))
    )
    (net (code "12") (name "/BUZZ") (class "Default")
      (node (ref "R3") (pin "1") (pinfunction "1_1") (pintype "passive"))
      (node (ref "U1") (pin "12") (pinfunction "PTA5_12") (pintype "passive"))
    )
    (net (code "13") (name "/COMPR") (class "Default")
      (node (ref "R28") (pin "1") (pinfunction "1_1") (pintype "passive"))
      (node (ref "U1") (pin "90") (pinfunction "PTF4/SDA/FB_D4/FB_AD10_90") (pintype "passive"))
    )
    (net (code "14") (name "/DB4") (class "Default")
      (node (ref "P1") (pin "11") (pinfunction "11_11") (pintype "passive"))
      (node (ref "U1") (pin "46") (pinfunction "PTH3/RGPIOP3/FB_D6_46") (pintype "passive"))
    )
    (net (code "15") (name "/DB5") (class "Default")
      (node (ref "P1") (pin "12") (pinfunction "12_12") (pintype "passive"))
      (node (ref "U1") (pin "47") (pinfunction "PTH4/RGPIOP4/FB_D5_47") (pintype "passive"))
    )
    (net (code "16") (name "/DB6") (class "Default")
      (node (ref "P1") (pin "13") (pinfunction "13_13") (pintype "passive"))
      (node (ref "U1") (pin "48") (pinfunction "PTH5/RGPIOP5/FB_D4_48") (pintype "passive"))
    )
    (net (code "17") (name "/DB7") (class "Default")
      (node (ref "P1") (pin "14") (pinfunction "14_14") (pintype "passive"))
      (node (ref "U1") (pin "49") (pinfunction "PTH6/RGPIOP6/FB_D3_49") (pintype "passive"))
    )
    (net (code "18") (name "/DPS") (class "Default")
      (node (ref "U1") (pin "10") (pinfunction "PTA3/KBI1P2/FB_D6/ADP5_10") (pintype "passive"))
      (node (ref "U1") (pin "19") (pinfunction "INP1-_19") (pintype "passive"))
      (node (ref "U1") (pin "20") (pinfunction "OUT1_20") (pintype "passive"))
    )
    (net (code "19") (name "/DPS2") (class "Default")
      (node (ref "U1") (pin "24") (pinfunction "INP2-_24") (pintype "passive"))
      (node (ref "U1") (pin "25") (pinfunction "OUT2_25") (pintype "passive"))
      (node (ref "U1") (pin "54") (pinfunction "PTC3/KBI1P6/SS2/ADP7_54") (pintype "passive"))
    )
    (net (code "20") (name "/E") (class "Default")
      (node (ref "P1") (pin "6") (pinfunction "6_6") (pintype "passive"))
      (node (ref "U1") (pin "45") (pinfunction "PTH2/RGPIOP2/FB_D7_45") (pintype "passive"))
    )
    (net (code "21") (name "/GAS1") (class "Default")
      (node (ref "R12") (pin "1") (pinfunction "1_1") (pintype "passive"))
      (node (ref "U1") (pin "81") (pinfunction "PTF0/USB_ID/TPM2CH2_81") (pintype "passive"))
    )
    (net (code "22") (name "/GAS2") (class "Default")
      (node (ref "R17") (pin "1") (pinfunction "1_1") (pintype "passive"))
      (node (ref "U1") (pin "82") (pinfunction "PTF1/RX2/USB_DP_DOWN/TPM2CH1_82") (pintype "passive"))
    )
    (net (code "23") (name "/MCU_RESET") (class "Default")
      (node (ref "C16") (pin "1") (pinfunction "1_1") (pintype "passive"))
      (node (ref "D7") (pin "2") (pinfunction "2_2") (pintype "passive"))
      (node (ref "P2") (pin "4") (pinfunction "4_4") (pintype "passive"))
      (node (ref "R26") (pin "1") (pinfunction "1_1") (pintype "passive"))
      (node (ref "S1") (pin "3") (pinfunction "3_3") (pintype "passive"))
      (node (ref "S1") (pin "4") (pinfunction "4_4") (pintype "passive"))
      (node (ref "U1") (pin "60") (pinfunction "PTD1/CMPP2/RESET_60") (pintype "passive"))
    )
    (net (code "24") (name "/OUTPUT") (class "Default")
      (node (ref "R7") (pin "1") (pinfunction "1_1") (pintype "passive"))
      (node (ref "U1") (pin "83") (pinfunction "PTF2/TX2/USB_DM_DOWN/TPM2CH0_83") (pintype "passive"))
    )
    (net (code "25") (name "/P1S") (class "Default")
      (node (ref "U1") (pin "53") (pinfunction "PTC2/KBI1P5/SPSCK2/ADP6_53") (pintype "passive"))
      (node (ref "U3") (pin "4") (pinfunction "VOUT_4") (pintype "output"))
    )
    (net (code "26") (name "/P2S") (class "Default")
      (node (ref "U1") (pin "55") (pinfunction "PTC4/KBI1P7/CMPP0/ADP8_55") (pintype "passive"))
      (node (ref "U4") (pin "4") (pinfunction "VOUT_4") (pintype "output"))
    )
    (net (code "27") (name "/RESIDUAL") (class "Default")
      (node (ref "R22") (pin "1") (pinfunction "1_1") (pintype "passive"))
      (node (ref "U1") (pin "89") (pinfunction "PTF3/SCL/FB_D5/FB_AD11_89") (pintype "passive"))
    )
    (net (code "28") (name "/RS") (class "Default")
      (node (ref "P1") (pin "4") (pinfunction "4_4") (pintype "passive"))
      (node (ref "U1") (pin "6") (pinfunction "PTH0/FB_OE_6") (pintype "passive"))
    )
    (net (code "29") (name "/R{slash}W") (class "Default")
      (node (ref "P1") (pin "5") (pinfunction "5_5") (pintype "passive"))
      (node (ref "U1") (pin "7") (pinfunction "PTH1/FB_D0_7") (pintype "passive"))
    )
    (net (code "30") (name "/TEMP") (class "Default")
      (node (ref "U1") (pin "9") (pinfunction "PTA2/KBI1P1/RX1/ADP4_9") (pintype "passive"))
      (node (ref "U2") (pin "3") (pinfunction "OUT_3") (pintype "output"))
    )
    (net (code "31") (name "/USB_ID_N") (class "Default")
      (node (ref "R29") (pin "2") (pinfunction "2_2") (pintype "passive"))
      (node (ref "U1") (pin "93") (pinfunction "USB_DM_93") (pintype "passive"))
    )
    (net (code "32") (name "/USB_ID_P") (class "Default")
      (node (ref "R30") (pin "2") (pinfunction "2_2") (pintype "passive"))
      (node (ref "U1") (pin "94") (pinfunction "USB_DP_94") (pintype "passive"))
    )
    (net (code "33") (name "/USB_N") (class "Default")
      (node (ref "J1") (pin "2") (pinfunction "D-_2") (pintype "bidirectional"))
      (node (ref "R29") (pin "1") (pinfunction "1_1") (pintype "passive"))
    )
    (net (code "34") (name "/USB_P") (class "Default")
      (node (ref "J1") (pin "3") (pinfunction "D+_3") (pintype "bidirectional"))
      (node (ref "R30") (pin "1") (pinfunction "1_1") (pintype "passive"))
    )
    (net (code "35") (name "/VO") (class "Default")
      (node (ref "C1") (pin "1") (pinfunction "1_1") (pintype "passive"))
      (node (ref "P1") (pin "3") (pinfunction "3_3") (pintype "passive"))
      (node (ref "R2") (pin "2") (pinfunction "2_2") (pintype "passive"))
    )
    (net (code "36") (name "/VUSB33") (class "Default")
      (node (ref "C28") (pin "2") (pinfunction "2_2") (pintype "passive"))
      (node (ref "C29") (pin "2") (pinfunction "2_2") (pintype "passive"))
      (node (ref "U1") (pin "92") (pinfunction "VUSB33_92") (pintype "passive"))
    )
    (net (code "37") (name "/V_USB_BUS") (class "Default")
      (node (ref "C30") (pin "2") (pinfunction "2_2") (pintype "passive"))
      (node (ref "FB1") (pin "2") (pinfunction "2_2") (pintype "passive"))
      (node (ref "U1") (pin "95") (pinfunction "VBUS_95") (pintype "passive"))
    )
    (net (code "38") (name "AGND") (class "Default")
      (node (ref "C27") (pin "2") (pinfunction "2_2") (pintype "passive"))
      (node (ref "FB5") (pin "1") (pinfunction "1_1") (pintype "passive"))
      (node (ref "U1") (pin "17") (pinfunction "VSSA_17") (pintype "passive"))
      (node (ref "U1") (pin "18") (pinfunction "VREFL_18") (pintype "passive"))
    )
    (net (code "39") (name "GND") (class "Default")
      (node (ref "C1") (pin "2") (pinfunction "2_2") (pintype "passive"))
      (node (ref "C10") (pin "2") (pinfunction "2_2") (pintype "passive"))
      (node (ref "C11") (pin "2") (pinfunction "2_2") (pintype "passive"))
      (node (ref "C12") (pin "2") (pinfunction "2_2") (pintype "passive"))
      (node (ref "C13") (pin "2") (pinfunction "2_2") (pintype "passive"))
      (node (ref "C14") (pin "2") (pinfunction "2_2") (pintype "passive"))
      (node (ref "C15") (pin "2") (pinfunction "2_2") (pintype "passive"))
      (node (ref "C16") (pin "2") (pinfunction "2_2") (pintype "passive"))
      (node (ref "C17") (pin "2") (pinfunction "2_2") (pintype "passive"))
      (node (ref "C18") (pin "2") (pinfunction "2_2") (pintype "passive"))
      (node (ref "C19") (pin "2") (pinfunction "2_2") (pintype "passive"))
      (node (ref "C2") (pin "2") (pinfunction "2_2") (pintype "passive"))
      (node (ref "C20") (pin "2") (pinfunction "2_2") (pintype "passive"))
      (node (ref "C21") (pin "2") (pinfunction "2_2") (pintype "passive"))
      (node (ref "C22") (pin "2") (pinfunction "2_2") (pintype "passive"))
      (node (ref "C23") (pin "2") (pinfunction "2_2") (pintype "passive"))
      (node (ref "C24") (pin "2") (pinfunction "2_2") (pintype "passive"))
      (node (ref "C25") (pin "2") (pinfunction "2_2") (pintype "passive"))
      (node (ref "C26") (pin "2") (pinfunction "2_2") (pintype "passive"))
      (node (ref "C28") (pin "1") (pinfunction "1_1") (pintype "passive"))
      (node (ref "C29") (pin "1") (pinfunction "1_1") (pintype "passive"))
      (node (ref "C3") (pin "2") (pinfunction "2_2") (pintype "passive"))
      (node (ref "C30") (pin "1") (pinfunction "1_1") (pintype "passive"))
      (node (ref "C4") (pin "2") (pinfunction "2_2") (pintype "passive"))
      (node (ref "C5") (pin "2") (pinfunction "2_2") (pintype "passive"))
      (node (ref "C6") (pin "2") (pinfunction "2_2") (pintype "passive"))
      (node (ref "C7") (pin "2") (pinfunction "2_2") (pintype "passive"))
      (node (ref "C8") (pin "2") (pinfunction "2_2") (pintype "passive"))
      (node (ref "C9") (pin "2") (pinfunction "2_2") (pintype "passive"))
      (node (ref "D10") (pin "1") (pinfunction "1_1") (pintype "passive"))
      (node (ref "D2") (pin "2") (pinfunction "K_2") (pintype "passive"))
      (node (ref "FB2") (pin "2") (pinfunction "2_2") (pintype "passive"))
      (node (ref "FB5") (pin "2") (pinfunction "2_2") (pintype "passive"))
      (node (ref "J1") (pin "6") (pinfunction "MP1_6") (pintype "passive"))
      (node (ref "J1") (pin "7") (pinfunction "MP2_7") (pintype "passive"))
      (node (ref "J1") (pin "8") (pinfunction "MP3_8") (pintype "passive"))
      (node (ref "J1") (pin "9") (pinfunction "MP4_9") (pintype "passive"))
      (node (ref "J7") (pin "2") (pinfunction "2_2") (pintype "passive"))
      (node (ref "P1") (pin "1") (pinfunction "1_1") (pintype "passive"))
      (node (ref "P1") (pin "16") (pinfunction "16_16") (pintype "passive"))
      (node (ref "P2") (pin "2") (pinfunction "2_2") (pintype "passive"))
      (node (ref "P3") (pin "5") (pinfunction "5_5") (pintype "passive"))
      (node (ref "P3") (pin "6") (pinfunction "6_6") (pintype "passive"))
      (node (ref "Q1") (pin "2") (pinfunction "E_2") (pintype "passive"))
      (node (ref "Q2") (pin "1") (pinfunction "S_1") (pintype "passive"))
      (node (ref "Q2") (pin "2") (pinfunction "S_2") (pintype "passive"))
      (node (ref "Q2") (pin "3") (pinfunction "S_3") (pintype "passive"))
      (node (ref "Q3") (pin "1") (pinfunction "S_1") (pintype "passive"))
      (node (ref "Q3") (pin "2") (pinfunction "S_2") (pintype "passive"))
      (node (ref "Q3") (pin "3") (pinfunction "S_3") (pintype "passive"))
      (node (ref "Q4") (pin "1") (pinfunction "S_1") (pintype "passive"))
      (node (ref "Q4") (pin "2") (pinfunction "S_2") (pintype "passive"))
      (node (ref "Q4") (pin "3") (pinfunction "S_3") (pintype "passive"))
      (node (ref "Q5") (pin "1") (pinfunction "S_1") (pintype "passive"))
      (node (ref "Q5") (pin "2") (pinfunction "S_2") (pintype "passive"))
      (node (ref "Q5") (pin "3") (pinfunction "S_3") (pintype "passive"))
      (node (ref "R11") (pin "1") (pinfunction "1_1") (pintype "passive"))
      (node (ref "R14") (pin "2") (pinfunction "2_2") (pintype "passive"))
      (node (ref "R15") (pin "1") (pinfunction "1_1") (pintype "passive"))
      (node (ref "R19") (pin "2") (pinfunction "2_2") (pintype "passive"))
      (node (ref "R2") (pin "1") (pinfunction "1_1") (pintype "passive"))
      (node (ref "R20") (pin "1") (pinfunction "1_1") (pintype "passive"))
      (node (ref "R21") (pin "1") (pinfunction "1_1") (pintype "passive"))
      (node (ref "R24") (pin "2") (pinfunction "2_2") (pintype "passive"))
      (node (ref "R25") (pin "1") (pinfunction "1_1") (pintype "passive"))
      (node (ref "R4") (pin "2") (pinfunction "2_2") (pintype "passive"))
      (node (ref "R8") (pin "1") (pinfunction "1_1") (pintype "passive"))
      (node (ref "R9") (pin "2") (pinfunction "2_2") (pintype "passive"))
      (node (ref "S1") (pin "1") (pinfunction "1_1") (pintype "passive"))
      (node (ref "S1") (pin "2") (pinfunction "2_2") (pintype "passive"))
      (node (ref "U1") (pin "37") (pinfunction "VSS2_37") (pintype "passive"))
      (node (ref "U1") (pin "76") (pinfunction "VSS3_76") (pintype "passive"))
      (node (ref "U1") (pin "96") (pinfunction "VSS1_96") (pintype "passive"))
      (node (ref "U2") (pin "2") (pinfunction "GND_2") (pintype "power_in"))
      (node (ref "U3") (pin "3") (pinfunction "GND_3") (pintype "power_in"))
      (node (ref "U4") (pin "3") (pinfunction "GND_3") (pintype "power_in"))
      (node (ref "U5") (pin "3") (pinfunction "GND_3") (pintype "power_in"))
      (node (ref "U6") (pin "3") (pinfunction "GND_3") (pintype "power_in"))
      (node (ref "U7") (pin "2") (pinfunction "K_2") (pintype "passive"))
      (node (ref "U7") (pin "4") (pinfunction "E_4") (pintype "passive"))
      (node (ref "U8") (pin "1") (pinfunction "GND_1") (pintype "power_in"))
      (node (ref "U9") (pin "1") (pinfunction "GND_1") (pintype "power_in"))
      (node (ref "X1") (pin "2") (pinfunction "GND_2") (pintype "power_in"))
    )
    (net (code "40") (name "MCU3V3") (class "Default")
      (node (ref "C17") (pin "1") (pinfunction "1_1") (pintype "passive"))
      (node (ref "C18") (pin "1") (pinfunction "1_1") (pintype "passive"))
      (node (ref "C19") (pin "1") (pinfunction "1_1") (pintype "passive"))
      (node (ref "C20") (pin "1") (pinfunction "1_1") (pintype "passive"))
      (node (ref "C3") (pin "1") (pinfunction "1_1") (pintype "passive"))
      (node (ref "C6") (pin "1") (pinfunction "1_1") (pintype "passive"))
      (node (ref "FB3") (pin "2") (pinfunction "2_2") (pintype "passive"))
      (node (ref "FB4") (pin "2") (pinfunction "2_2") (pintype "passive"))
      (node (ref "P2") (pin "6") (pinfunction "6_6") (pintype "passive"))
      (node (ref "R26") (pin "2") (pinfunction "2_2") (pintype "passive"))
      (node (ref "U1") (pin "35") (pinfunction "VREFH_35") (pintype "passive"))
      (node (ref "U1") (pin "40") (pinfunction "VDD2_40") (pintype "passive"))
      (node (ref "U1") (pin "77") (pinfunction "VDD3_77") (pintype "passive"))
      (node (ref "U1") (pin "97") (pinfunction "VDD1_97") (pintype "passive"))
    )
    (net (code "41") (name "Net-(D2-A)") (class "Default")
      (node (ref "D2") (pin "1") (pinfunction "A_1") (pintype "passive"))
      (node (ref "R5") (pin "2") (pinfunction "2_2") (pintype "passive"))
    )
    (net (code "42") (name "Net-(D3-Pad1)") (class "Default")
      (node (ref "D3") (pin "1") (pinfunction "1_1") (pintype "passive"))
      (node (ref "J2") (pin "2") (pinfunction "2_2") (pintype "passive"))
      (node (ref "Q2") (pin "5") (pinfunction "D_5") (pintype "passive"))
      (node (ref "Q2") (pin "6") (pinfunction "D_6") (pintype "passive"))
      (node (ref "Q2") (pin "7") (pinfunction "D_7") (pintype "passive"))
      (node (ref "Q2") (pin "8") (pinfunction "D_8") (pintype "passive"))
    )
    (net (code "43") (name "Net-(D4-Pad1)") (class "Default")
      (node (ref "D4") (pin "1") (pinfunction "1_1") (pintype "passive"))
      (node (ref "J3") (pin "2") (pinfunction "2_2") (pintype "passive"))
      (node (ref "Q3") (pin "5") (pinfunction "D_5") (pintype "passive"))
      (node (ref "Q3") (pin "6") (pinfunction "D_6") (pintype "passive"))
      (node (ref "Q3") (pin "7") (pinfunction "D_7") (pintype "passive"))
      (node (ref "Q3") (pin "8") (pinfunction "D_8") (pintype "passive"))
    )
    (net (code "44") (name "Net-(D5-Pad1)") (class "Default")
      (node (ref "D5") (pin "1") (pinfunction "1_1") (pintype "passive"))
      (node (ref "J4") (pin "2") (pinfunction "2_2") (pintype "passive"))
      (node (ref "Q4") (pin "5") (pinfunction "D_5") (pintype "passive"))
      (node (ref "Q4") (pin "6") (pinfunction "D_6") (pintype "passive"))
      (node (ref "Q4") (pin "7") (pinfunction "D_7") (pintype "passive"))
      (node (ref "Q4") (pin "8") (pinfunction "D_8") (pintype "passive"))
    )
    (net (code "45") (name "Net-(D6-Pad1)") (class "Default")
      (node (ref "D6") (pin "1") (pinfunction "1_1") (pintype "passive"))
      (node (ref "J5") (pin "2") (pinfunction "2_2") (pintype "passive"))
      (node (ref "Q5") (pin "5") (pinfunction "D_5") (pintype "passive"))
      (node (ref "Q5") (pin "6") (pinfunction "D_6") (pintype "passive"))
      (node (ref "Q5") (pin "7") (pinfunction "D_7") (pintype "passive"))
      (node (ref "Q5") (pin "8") (pinfunction "D_8") (pintype "passive"))
    )
    (net (code "46") (name "Net-(D7-Pad1)") (class "Default")
      (node (ref "D7") (pin "1") (pinfunction "1_1") (pintype "passive"))
      (node (ref "R27") (pin "2") (pinfunction "2_2") (pintype "passive"))
    )
    (net (code "47") (name "Net-(D9-Pad1)") (class "Default")
      (node (ref "D9") (pin "1") (pinfunction "1_1") (pintype "passive"))
      (node (ref "J7") (pin "1") (pinfunction "1_1") (pintype "passive"))
    )
    (net (code "48") (name "Net-(J1-GND)") (class "Default")
      (node (ref "FB2") (pin "1") (pinfunction "1_1") (pintype "passive"))
      (node (ref "J1") (pin "5") (pinfunction "GND_5") (pintype "power_in"))
    )
    (net (code "49") (name "Net-(J1-VBUS)") (class "Default")
      (node (ref "FB1") (pin "1") (pinfunction "1_1") (pintype "passive"))
      (node (ref "J1") (pin "1") (pinfunction "VBUS_1") (pintype "power_in"))
    )
    (net (code "50") (name "Net-(K1-COM)") (class "Default")
      (node (ref "J6") (pin "2") (pinfunction "2_2") (pintype "passive"))
      (node (ref "K1") (pin "1") (pinfunction "COM_1") (pintype "passive"))
    )
    (net (code "51") (name "Net-(K1-N.O.)") (class "Default")
      (node (ref "J6") (pin "1") (pinfunction "1_1") (pintype "passive"))
      (node (ref "K1") (pin "3") (pinfunction "N.O._3") (pintype "passive"))
    )
    (net (code "52") (name "Net-(Q1-B)") (class "Default")
      (node (ref "Q1") (pin "1") (pinfunction "B_1") (pintype "passive"))
      (node (ref "R3") (pin "2") (pinfunction "2_2") (pintype "passive"))
      (node (ref "R4") (pin "1") (pinfunction "1_1") (pintype "passive"))
    )
    (net (code "53") (name "Net-(Q1-C)") (class "Default")
      (node (ref "D1") (pin "1") (pinfunction "1_1") (pintype "passive"))
      (node (ref "LS1") (pin "2") (pinfunction "2_2") (pintype "passive"))
      (node (ref "Q1") (pin "3") (pinfunction "C_3") (pintype "passive"))
    )
    (net (code "54") (name "Net-(Q2-G)") (class "Default")
      (node (ref "Q2") (pin "4") (pinfunction "G_4") (pintype "passive"))
      (node (ref "R7") (pin "2") (pinfunction "2_2") (pintype "passive"))
      (node (ref "R9") (pin "1") (pinfunction "1_1") (pintype "passive"))
    )
    (net (code "55") (name "Net-(Q3-G)") (class "Default")
      (node (ref "Q3") (pin "4") (pinfunction "G_4") (pintype "passive"))
      (node (ref "R12") (pin "2") (pinfunction "2_2") (pintype "passive"))
      (node (ref "R14") (pin "1") (pinfunction "1_1") (pintype "passive"))
    )
    (net (code "56") (name "Net-(Q4-G)") (class "Default")
      (node (ref "Q4") (pin "4") (pinfunction "G_4") (pintype "passive"))
      (node (ref "R17") (pin "2") (pinfunction "2_2") (pintype "passive"))
      (node (ref "R19") (pin "1") (pinfunction "1_1") (pintype "passive"))
    )
    (net (code "57") (name "Net-(Q5-G)") (class "Default")
      (node (ref "Q5") (pin "4") (pinfunction "G_4") (pintype "passive"))
      (node (ref "R22") (pin "2") (pinfunction "2_2") (pintype "passive"))
      (node (ref "R24") (pin "1") (pinfunction "1_1") (pintype "passive"))
    )
    (net (code "58") (name "Net-(R1-Pad2)") (class "Default")
      (node (ref "R1") (pin "2") (pinfunction "2_2") (pintype "passive"))
      (node (ref "R2") (pin "3") (pinfunction "3_3") (pintype "passive"))
    )
    (net (code "59") (name "Net-(R6-Pad1)") (class "Default")
      (node (ref "R6") (pin "1") (pinfunction "1_1") (pintype "passive"))
      (node (ref "SW1") (pin "2") (pinfunction "2_2") (pintype "passive"))
    )
    (net (code "60") (name "Net-(R10-Pad1)") (class "Default")
      (node (ref "R10") (pin "1") (pinfunction "1_1") (pintype "passive"))
      (node (ref "SW2") (pin "2") (pinfunction "2_2") (pintype "passive"))
    )
    (net (code "61") (name "Net-(R13-Pad1)") (class "Default")
      (node (ref "R13") (pin "1") (pinfunction "1_1") (pintype "passive"))
      (node (ref "SW3") (pin "2") (pinfunction "2_2") (pintype "passive"))
    )
    (net (code "62") (name "Net-(R18-Pad1)") (class "Default")
      (node (ref "R18") (pin "1") (pinfunction "1_1") (pintype "passive"))
      (node (ref "SW4") (pin "2") (pinfunction "2_2") (pintype "passive"))
    )
    (net (code "63") (name "Net-(U1A-PTB4{slash}EXTAL2)") (class "Default")
      (node (ref "C14") (pin "1") (pinfunction "1_1") (pintype "passive"))
      (node (ref "U1") (pin "41") (pinfunction "PTB4/EXTAL2_41") (pintype "passive"))
      (node (ref "X1") (pin "1") (pinfunction "HOT_1") (pintype "passive"))
    )
    (net (code "64") (name "Net-(U1A-PTB5{slash}XTAL2)") (class "Default")
      (node (ref "C13") (pin "1") (pinfunction "1_1") (pintype "passive"))
      (node (ref "U1") (pin "42") (pinfunction "PTB5/XTAL2_42") (pintype "passive"))
      (node (ref "X1") (pin "3") (pinfunction "HOT_3") (pintype "passive"))
    )
    (net (code "65") (name "Net-(U1A-VREFO)") (class "Default")
      (node (ref "C7") (pin "1") (pinfunction "1_1") (pintype "passive"))
      (node (ref "U1") (pin "32") (pinfunction "VREFO_32") (pintype "passive"))
    )
    (net (code "66") (name "Net-(U1B-VDDA)") (class "Default")
      (node (ref "C27") (pin "1") (pinfunction "1_1") (pintype "passive"))
      (node (ref "FB4") (pin "1") (pinfunction "1_1") (pintype "passive"))
      (node (ref "U1") (pin "36") (pinfunction "VDDA_36") (pintype "passive"))
    )
    (net (code "67") (name "Net-(U2-GS1)") (class "Default")
      (node (ref "P3") (pin "3") (pinfunction "3_3") (pintype "passive"))
      (node (ref "U2") (pin "5") (pinfunction "GS1_5") (pintype "input"))
    )
    (net (code "68") (name "Net-(U2-GSO)") (class "Default")
      (node (ref "P3") (pin "4") (pinfunction "4_4") (pintype "passive"))
      (node (ref "U2") (pin "1") (pinfunction "GSO_1") (pintype "input"))
    )
    (net (code "69") (name "Net-(U5-VOUT)") (class "Default")
      (node (ref "R16") (pin "2") (pinfunction "2_2") (pintype "passive"))
      (node (ref "U5") (pin "4") (pinfunction "VOUT_4") (pintype "output"))
    )
    (net (code "70") (name "Net-(U6-VOUT)") (class "Default")
      (node (ref "R23") (pin "2") (pinfunction "2_2") (pintype "passive"))
      (node (ref "U6") (pin "4") (pinfunction "VOUT_4") (pintype "output"))
    )
    (net (code "71") (name "Net-(U7-A)") (class "Default")
      (node (ref "R28") (pin "2") (pinfunction "2_2") (pintype "passive"))
      (node (ref "U7") (pin "1") (pinfunction "A_1") (pintype "passive"))
    )
    (net (code "72") (name "Net-(U7-C)") (class "Default")
      (node (ref "D8") (pin "1") (pinfunction "1_1") (pintype "passive"))
      (node (ref "K1") (pin "5") (pinfunction "5_5") (pintype "passive"))
      (node (ref "U7") (pin "5") (pinfunction "C_5") (pintype "passive"))
    )
    (net (code "73") (name "Net-(U8-IN)") (class "Default")
      (node (ref "C21") (pin "1") (pinfunction "1_1") (pintype "passive"))
      (node (ref "C22") (pin "1") (pinfunction "1_1") (pintype "passive"))
      (node (ref "D10") (pin "2") (pinfunction "2_2") (pintype "passive"))
      (node (ref "D9") (pin "2") (pinfunction "2_2") (pintype "passive"))
      (node (ref "U8") (pin "3") (pinfunction "IN_3") (pintype "power_in"))
    )
    (net (code "74") (name "unconnected-(J1-ID-Pad4)") (class "Default")
      (node (ref "J1") (pin "4") (pinfunction "ID_4") (pintype "passive+no_connect"))
    )
    (net (code "75") (name "unconnected-(K1-N.C.-Pad4)") (class "Default")
      (node (ref "K1") (pin "4") (pinfunction "N.C._4") (pintype "passive"))
    )
    (net (code "76") (name "unconnected-(P1-Pad7)") (class "Default")
      (node (ref "P1") (pin "7") (pinfunction "7_7") (pintype "passive"))
    )
    (net (code "77") (name "unconnected-(P1-Pad8)") (class "Default")
      (node (ref "P1") (pin "8") (pinfunction "8_8") (pintype "passive"))
    )
    (net (code "78") (name "unconnected-(P1-Pad9)") (class "Default")
      (node (ref "P1") (pin "9") (pinfunction "9_9") (pintype "passive"))
    )
    (net (code "79") (name "unconnected-(P1-Pad10)") (class "Default")
      (node (ref "P1") (pin "10") (pinfunction "10_10") (pintype "passive"))
    )
    (net (code "80") (name "unconnected-(P2-Pad3)") (class "Default")
      (node (ref "P2") (pin "3") (pinfunction "3_3") (pintype "passive"))
    )
    (net (code "81") (name "unconnected-(P2-Pad5)") (class "Default")
      (node (ref "P2") (pin "5") (pinfunction "5_5") (pintype "passive"))
    )
    (net (code "82") (name "unconnected-(U1A-DACO-Pad26)") (class "Default")
      (node (ref "U1") (pin "26") (pinfunction "DACO_26") (pintype "passive+no_connect"))
    )
    (net (code "83") (name "unconnected-(U1A-DADM0-Pad31)") (class "Default")
      (node (ref "U1") (pin "31") (pinfunction "DADM0_31") (pintype "passive+no_connect"))
    )
    (net (code "84") (name "unconnected-(U1A-DADM1-Pad34)") (class "Default")
      (node (ref "U1") (pin "34") (pinfunction "DADM1_34") (pintype "passive+no_connect"))
    )
    (net (code "85") (name "unconnected-(U1A-DADM2{slash}VINN1-Pad23)") (class "Default")
      (node (ref "U1") (pin "23") (pinfunction "DADM2/VINN1_23") (pintype "passive+no_connect"))
    )
    (net (code "86") (name "unconnected-(U1A-DADM3{slash}VINN2-Pad29)") (class "Default")
      (node (ref "U1") (pin "29") (pinfunction "DADM3/VINN2_29") (pintype "passive+no_connect"))
    )
    (net (code "87") (name "unconnected-(U1A-DADP0-Pad30)") (class "Default")
      (node (ref "U1") (pin "30") (pinfunction "DADP0_30") (pintype "passive+no_connect"))
    )
    (net (code "88") (name "unconnected-(U1A-DADP1-Pad33)") (class "Default")
      (node (ref "U1") (pin "33") (pinfunction "DADP1_33") (pintype "passive+no_connect"))
    )
    (net (code "89") (name "unconnected-(U1A-DADP2{slash}TRIOUT1-Pad21)") (class "Default")
      (node (ref "U1") (pin "21") (pinfunction "DADP2/TRIOUT1_21") (pintype "passive+no_connect"))
    )
    (net (code "90") (name "unconnected-(U1A-DADP3{slash}TRIOUT2-Pad27)") (class "Default")
      (node (ref "U1") (pin "27") (pinfunction "DADP3/TRIOUT2_27") (pintype "passive+no_connect"))
    )
    (net (code "91") (name "unconnected-(U1A-FB_AD12-Pad88)") (class "Default")
      (node (ref "U1") (pin "88") (pinfunction "FB_AD12_88") (pintype "passive+no_connect"))
    )
    (net (code "92") (name "unconnected-(U1A-IRO-Pad2)") (class "Default")
      (node (ref "U1") (pin "2") (pinfunction "IRO_2") (pintype "passive+no_connect"))
    )
    (net (code "93") (name "unconnected-(U1A-PTA0{slash}FB_D2{slash}SS1-Pad1)") (class "Default")
      (node (ref "U1") (pin "1") (pinfunction "PTA0/FB_D2/SS1_1") (pintype "passive+no_connect"))
    )
    (net (code "94") (name "unconnected-(U1A-PTA1{slash}KBI1P0{slash}TX1{slash}FB_D1-Pad8)") (class "Default")
      (node (ref "U1") (pin "8") (pinfunction "PTA1/KBI1P0/TX1/FB_D1_8") (pintype "passive+no_connect"))
    )
    (net (code "95") (name "unconnected-(U1A-PTB0-Pad15)") (class "Default")
      (node (ref "U1") (pin "15") (pinfunction "PTB0_15") (pintype "passive+no_connect"))
    )
    (net (code "96") (name "unconnected-(U1A-PTB1{slash}BLMS-Pad16)") (class "Default")
      (node (ref "U1") (pin "16") (pinfunction "PTB1/BLMS_16") (pintype "passive+no_connect"))
    )
    (net (code "97") (name "unconnected-(U1A-PTB2{slash}EXTAL1-Pad38)") (class "Default")
      (node (ref "U1") (pin "38") (pinfunction "PTB2/EXTAL1_38") (pintype "passive+no_connect"))
    )
    (net (code "98") (name "unconnected-(U1A-PTB3{slash}XTAL1-Pad39)") (class "Default")
      (node (ref "U1") (pin "39") (pinfunction "PTB3/XTAL1_39") (pintype "passive+no_connect"))
    )
    (net (code "99") (name "unconnected-(U1A-PTB6{slash}KBI1P3{slash}RGPIOP0{slash}FB_AD17-Pad43)") (class "Default")
      (node (ref "U1") (pin "43") (pinfunction "PTB6/KBI1P3/RGPIOP0/FB_AD17_43") (pintype "passive+no_connect"))
    )
    (net (code "100") (name "unconnected-(U1A-PTB7{slash}KBI1P4{slash}RGPIOP1{slash}FB_AD0-Pad44)") (class "Default")
      (node (ref "U1") (pin "44") (pinfunction "PTB7/KBI1P4/RGPIOP1/FB_AD0_44") (pintype "passive+no_connect"))
    )
    (net (code "101") (name "unconnected-(U1A-PTC0{slash}MOSI2{slash}FB_OE{slash}FB_CS0-Pad51)") (class "Default")
      (node (ref "U1") (pin "51") (pinfunction "PTC0/MOSI2/FB_OE/FB_CS0_51") (pintype "passive+no_connect"))
    )
    (net (code "102") (name "unconnected-(U1A-PTC1{slash}MISO2{slash}FB_D0{slash}FB_AD1-Pad52)") (class "Default")
      (node (ref "U1") (pin "52") (pinfunction "PTC1/MISO2/FB_D0/FB_AD1_52") (pintype "passive+no_connect"))
    )
    (net (code "103") (name "unconnected-(U1A-PTC5{slash}KBI2P0{slash}CMPP1{slash}ADP9-Pad56)") (class "Default")
      (node (ref "U1") (pin "56") (pinfunction "PTC5/KBI2P0/CMPP1/ADP9_56") (pintype "passive+no_connect"))
    )
    (net (code "104") (name "unconnected-(U1A-PTC6{slash}KBI2P1{slash}PRACMPO{slash}ADP10-Pad57)") (class "Default")
      (node (ref "U1") (pin "57") (pinfunction "PTC6/KBI2P1/PRACMPO/ADP10_57") (pintype "passive+no_connect"))
    )
    (net (code "105") (name "unconnected-(U1A-PTC7{slash}KBI2P2{slash}CLKOUT{slash}ADP11-Pad58)") (class "Default")
      (node (ref "U1") (pin "58") (pinfunction "PTC7/KBI2P2/CLKOUT/ADP11_58") (pintype "passive+no_connect"))
    )
    (net (code "106") (name "unconnected-(U1A-PTD2{slash}USB_ALTCLK{slash}RGPIOP8{slash}TPM1CH0-Pad61)") (class "Default")
      (node (ref "U1") (pin "61") (pinfunction "PTD2/USB_ALTCLK/RGPIOP8/TPM1CH0_61") (pintype "passive+no_connect"))
    )
    (net (code "107") (name "unconnected-(U1A-PTD3{slash}USB_PULLUP(D+){slash}RGPIOP9{slash}TPM1CH1-Pad62)") (class "Default")
      (node (ref "U1") (pin "62") (pinfunction "PTD3/USB_PULLUP(D+)/RGPIOP9/TPM1CH1_62") (pintype "passive+no_connect"))
    )
    (net (code "108") (name "unconnected-(U1A-PTD4{slash}SDA{slash}RGPIOP10{slash}TPM1CH2-Pad63)") (class "Default")
      (node (ref "U1") (pin "63") (pinfunction "PTD4/SDA/RGPIOP10/TPM1CH2_63") (pintype "passive+no_connect"))
    )
    (net (code "109") (name "unconnected-(U1A-PTD5{slash}SCL{slash}RGPIOP11{slash}TPM1CH3-Pad64)") (class "Default")
      (node (ref "U1") (pin "64") (pinfunction "PTD5/SCL/RGPIOP11/TPM1CH3_64") (pintype "passive+no_connect"))
    )
    (net (code "110") (name "unconnected-(U1A-PTD6{slash}USB_ALTCLK{slash}TX1-Pad65)") (class "Default")
      (node (ref "U1") (pin "65") (pinfunction "PTD6/USB_ALTCLK/TX1_65") (pintype "passive+no_connect"))
    )
    (net (code "111") (name "unconnected-(U1A-PTD7{slash}USB_PULLUP(D+)_{slash}RX1-Pad66)") (class "Default")
      (node (ref "U1") (pin "66") (pinfunction "PTD7/USB_PULLUP(D+)_/RX1_66") (pintype "passive+no_connect"))
    )
    (net (code "112") (name "unconnected-(U1A-PTE4{slash}CMPP3{slash}TPMCLK{slash}IRQ-Pad75)") (class "Default")
      (node (ref "U1") (pin "75") (pinfunction "PTE4/CMPP3/TPMCLK/IRQ_75") (pintype "passive+no_connect"))
    )
    (net (code "113") (name "unconnected-(U1A-PTE5{slash}FB_D7{slash}USB_SESSVLD{slash}TX2-Pad78)") (class "Default")
      (node (ref "U1") (pin "78") (pinfunction "PTE5/FB_D7/USB_SESSVLD/TX2_78") (pintype "passive+no_connect"))
    )
    (net (code "114") (name "unconnected-(U1A-PTE6{slash}FB_RW{slash}USB_SESSEND{slash}RX2-Pad79)") (class "Default")
      (node (ref "U1") (pin "79") (pinfunction "PTE6/FB_RW/USB_SESSEND/RX2_79") (pintype "passive+no_connect"))
    )
    (net (code "115") (name "unconnected-(U1A-PTE7{slash}USB_VBUSVLD{slash}TPM2CH3-Pad80)") (class "Default")
      (node (ref "U1") (pin "80") (pinfunction "PTE7/USB_VBUSVLD/TPM2CH3_80") (pintype "passive+no_connect"))
    )
    (net (code "116") (name "unconnected-(U1A-PTF5{slash}KBI2P7{slash}FB_D3{slash}FB_AD9-Pad91)") (class "Default")
      (node (ref "U1") (pin "91") (pinfunction "PTF5/KBI2P7/FB_D3/FB_AD9_91") (pintype "passive+no_connect"))
    )
    (net (code "117") (name "unconnected-(U1A-PTF6{slash}MOSI1-Pad98)") (class "Default")
      (node (ref "U1") (pin "98") (pinfunction "PTF6/MOSI1_98") (pintype "passive+no_connect"))
    )
    (net (code "118") (name "unconnected-(U1A-PTF7{slash}MISO1-Pad99)") (class "Default")
      (node (ref "U1") (pin "99") (pinfunction "PTF7/MISO1_99") (pintype "passive+no_connect"))
    )
    (net (code "119") (name "unconnected-(U1A-PTG0{slash}SPSCK1-Pad100)") (class "Default")
      (node (ref "U1") (pin "100") (pinfunction "PTG0/SPSCK1_100") (pintype "passive+no_connect"))
    )
    (net (code "120") (name "unconnected-(U1A-PTG5{slash}FB_RW-Pad3)") (class "Default")
      (node (ref "U1") (pin "3") (pinfunction "PTG5/FB_RW_3") (pintype "passive+no_connect"))
    )
    (net (code "121") (name "unconnected-(U1A-PTG6{slash}FB_AD19-Pad4)") (class "Default")
      (node (ref "U1") (pin "4") (pinfunction "PTG6/FB_AD19_4") (pintype "passive+no_connect"))
    )
    (net (code "122") (name "unconnected-(U1A-PTG7{slash}FB_AD18-Pad5)") (class "Default")
      (node (ref "U1") (pin "5") (pinfunction "PTG7/FB_AD18_5") (pintype "passive+no_connect"))
    )
    (net (code "123") (name "unconnected-(U1A-PTH7{slash}RGPIOP7{slash}FB_D2-Pad50)") (class "Default")
      (node (ref "U1") (pin "50") (pinfunction "PTH7/RGPIOP7/FB_D2_50") (pintype "passive+no_connect"))
    )
    (net (code "124") (name "unconnected-(U1A-PTJ0{slash}FB_AD2-Pad68)") (class "Default")
      (node (ref "U1") (pin "68") (pinfunction "PTJ0/FB_AD2_68") (pintype "passive+no_connect"))
    )
    (net (code "125") (name "unconnected-(U1A-PTJ1{slash}FB_AD3-Pad69)") (class "Default")
      (node (ref "U1") (pin "69") (pinfunction "PTJ1/FB_AD3_69") (pintype "passive+no_connect"))
    )
    (net (code "126") (name "unconnected-(U1A-PTJ2{slash}FB_AD4-Pad70)") (class "Default")
      (node (ref "U1") (pin "70") (pinfunction "PTJ2/FB_AD4_70") (pintype "passive+no_connect"))
    )
    (net (code "127") (name "unconnected-(U1A-PTJ3{slash}RGPIOP12{slash}FB_AD5-Pad71)") (class "Default")
      (node (ref "U1") (pin "71") (pinfunction "PTJ3/RGPIOP12/FB_AD5_71") (pintype "passive+no_connect"))
    )
    (net (code "128") (name "unconnected-(U1A-PTJ4{slash}RGPIOP15{slash}FB_AD16-Pad84)") (class "Default")
      (node (ref "U1") (pin "84") (pinfunction "PTJ4/RGPIOP15/FB_AD16_84") (pintype "passive+no_connect"))
    )
    (net (code "129") (name "unconnected-(U1A-PTJ5{slash}FB_AD15-Pad85)") (class "Default")
      (node (ref "U1") (pin "85") (pinfunction "PTJ5/FB_AD15_85") (pintype "passive+no_connect"))
    )
    (net (code "130") (name "unconnected-(U1A-PTJ6{slash}FB_AD14-Pad86)") (class "Default")
      (node (ref "U1") (pin "86") (pinfunction "PTJ6/FB_AD14_86") (pintype "passive+no_connect"))
    )
    (net (code "131") (name "unconnected-(U1A-PTJ7{slash}FB_AD13-Pad87)") (class "Default")
      (node (ref "U1") (pin "87") (pinfunction "PTJ7/FB_AD13_87") (pintype "passive+no_connect"))
    )
    (net (code "132") (name "unconnected-(U1A-VINP1-Pad22)") (class "Default")
      (node (ref "U1") (pin "22") (pinfunction "VINP1_22") (pintype "passive+no_connect"))
    )
    (net (code "133") (name "unconnected-(U1A-VINP2-Pad28)") (class "Default")
      (node (ref "U1") (pin "28") (pinfunction "VINP2_28") (pintype "passive+no_connect"))
    )
    (net (code "134") (name "unconnected-(U3-NC-Pad1)") (class "Default")
      (node (ref "U3") (pin "1") (pinfunction "NC_1") (pintype "passive"))
    )
    (net (code "135") (name "unconnected-(U3-NC-Pad5)") (class "Default")
      (node (ref "U3") (pin "5") (pinfunction "NC_5") (pintype "passive"))
    )
    (net (code "136") (name "unconnected-(U3-NC-Pad6)") (class "Default")
      (node (ref "U3") (pin "6") (pinfunction "NC_6") (pintype "passive"))
    )
    (net (code "137") (name "unconnected-(U3-NC-Pad7)") (class "Default")
      (node (ref "U3") (pin "7") (pinfunction "NC_7") (pintype "passive"))
    )
    (net (code "138") (name "unconnected-(U3-NC-Pad8)") (class "Default")
      (node (ref "U3") (pin "8") (pinfunction "NC_8") (pintype "passive"))
    )
    (net (code "139") (name "unconnected-(U4-NC-Pad1)") (class "Default")
      (node (ref "U4") (pin "1") (pinfunction "NC_1") (pintype "passive"))
    )
    (net (code "140") (name "unconnected-(U4-NC-Pad5)") (class "Default")
      (node (ref "U4") (pin "5") (pinfunction "NC_5") (pintype "passive"))
    )
    (net (code "141") (name "unconnected-(U4-NC-Pad6)") (class "Default")
      (node (ref "U4") (pin "6") (pinfunction "NC_6") (pintype "passive"))
    )
    (net (code "142") (name "unconnected-(U4-NC-Pad7)") (class "Default")
      (node (ref "U4") (pin "7") (pinfunction "NC_7") (pintype "passive"))
    )
    (net (code "143") (name "unconnected-(U4-NC-Pad8)") (class "Default")
      (node (ref "U4") (pin "8") (pinfunction "NC_8") (pintype "passive"))
    )
    (net (code "144") (name "unconnected-(U5-NC-Pad1)") (class "Default")
      (node (ref "U5") (pin "1") (pinfunction "NC_1") (pintype "passive"))
    )
    (net (code "145") (name "unconnected-(U5-NC-Pad5)") (class "Default")
      (node (ref "U5") (pin "5") (pinfunction "NC_5") (pintype "passive"))
    )
    (net (code "146") (name "unconnected-(U5-NC-Pad6)") (class "Default")
      (node (ref "U5") (pin "6") (pinfunction "NC_6") (pintype "passive"))
    )
    (net (code "147") (name "unconnected-(U5-NC-Pad7)") (class "Default")
      (node (ref "U5") (pin "7") (pinfunction "NC_7") (pintype "passive"))
    )
    (net (code "148") (name "unconnected-(U5-NC-Pad8)") (class "Default")
      (node (ref "U5") (pin "8") (pinfunction "NC_8") (pintype "passive"))
    )
    (net (code "149") (name "unconnected-(U6-NC-Pad1)") (class "Default")
      (node (ref "U6") (pin "1") (pinfunction "NC_1") (pintype "passive"))
    )
    (net (code "150") (name "unconnected-(U6-NC-Pad5)") (class "Default")
      (node (ref "U6") (pin "5") (pinfunction "NC_5") (pintype "passive"))
    )
    (net (code "151") (name "unconnected-(U6-NC-Pad6)") (class "Default")
      (node (ref "U6") (pin "6") (pinfunction "NC_6") (pintype "passive"))
    )
    (net (code "152") (name "unconnected-(U6-NC-Pad7)") (class "Default")
      (node (ref "U6") (pin "7") (pinfunction "NC_7") (pintype "passive"))
    )
    (net (code "153") (name "unconnected-(U6-NC-Pad8)") (class "Default")
      (node (ref "U6") (pin "8") (pinfunction "NC_8") (pintype "passive"))
    )
    (net (code "154") (name "unconnected-(U7-B-Pad6)") (class "Default")
      (node (ref "U7") (pin "6") (pinfunction "B_6") (pintype "passive"))
    )
    (net (code "155") (name "unconnected-(X1-NC-Pad4)") (class "Default")
      (node (ref "X1") (pin "4") (pinfunction "NC_4") (pintype "passive"))
    )
  )
)
